# miniboard-schem.net
KiCad netlist of a schematic drawn in EAGLE
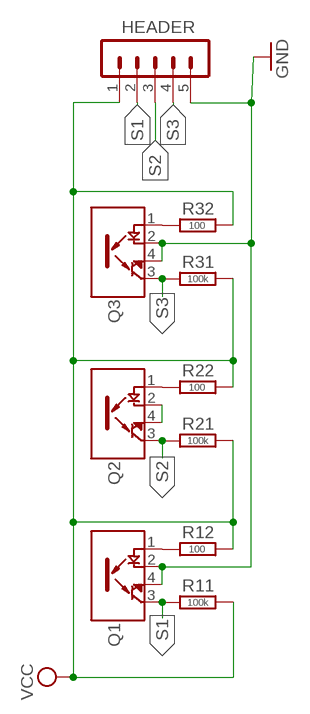
[diagram p0: schematic, sheet 1]

(export (version "E")
  (design (tool "Eeschema 10.0.6"))
  (components
    (comp (ref "HEADER")
      (value "0")
      (footprint "eagle-import:MA05-1")
      (libsource (lib "eagle-import") (part "MA05-1"))
    )
    (comp (ref "Q1")
      (value "QRE1113")
      (footprint "eagle-import:DIP400W50P180L360H200Q4")
      (fields (field (name "MANUFACTURER") "On Semiconductor"))
      (libsource (lib "eagle-import") (part "QRE1113"))
    )
    (comp (ref "Q2")
      (value "QRE1113")
      (footprint "eagle-import:DIP400W50P180L360H200Q4")
      (fields (field (name "MANUFACTURER") "On Semiconductor"))
      (libsource (lib "eagle-import") (part "QRE1113"))
    )
    (comp (ref "Q3")
      (value "QRE1113")
      (footprint "eagle-import:DIP400W50P180L360H200Q4")
      (fields (field (name "MANUFACTURER") "On Semiconductor"))
      (libsource (lib "eagle-import") (part "QRE1113"))
    )
    (comp (ref "R11")
      (value "100k")
      (footprint "eagle-import:0207_10")
      (libsource (lib "eagle-import") (part "R-EU_0207/10"))
    )
    (comp (ref "R12")
      (value "100")
      (footprint "eagle-import:0207_10")
      (libsource (lib "eagle-import") (part "R-EU_0207/10"))
    )
    (comp (ref "R21")
      (value "100k")
      (footprint "eagle-import:0207_10")
      (libsource (lib "eagle-import") (part "R-EU_0207/10"))
    )
    (comp (ref "R22")
      (value "100")
      (footprint "eagle-import:0207_10")
      (libsource (lib "eagle-import") (part "R-EU_0207/10"))
    )
    (comp (ref "R31")
      (value "100k")
      (footprint "eagle-import:0207_10")
      (libsource (lib "eagle-import") (part "R-EU_0207/10"))
    )
    (comp (ref "R32")
      (value "100")
      (footprint "eagle-import:0207_10")
      (libsource (lib "eagle-import") (part "R-EU_0207/10"))
    )
  )
  (nets
    (net (code "1") (name "GND") (class "Default")
      (node (ref "HEADER") (pin "5") (pinfunction "5_5") (pintype "passive"))
      (node (ref "Q1") (pin "2") (pinfunction "C_2") (pintype "passive"))
      (node (ref "Q1") (pin "4") (pinfunction "ET_4") (pintype "passive"))
      (node (ref "Q3") (pin "2") (pinfunction "C_2") (pintype "passive"))
      (node (ref "Q3") (pin "4") (pinfunction "ET_4") (pintype "passive"))
    )
    (net (code "2") (name "Net-(Q1-A)") (class "Default")
      (node (ref "Q1") (pin "1") (pinfunction "A_1") (pintype "passive"))
      (node (ref "R12") (pin "2") (pinfunction "2_2") (pintype "passive"))
    )
    (net (code "3") (name "Net-(Q2-A)") (class "Default")
      (node (ref "Q2") (pin "1") (pinfunction "A_1") (pintype "passive"))
      (node (ref "R22") (pin "2") (pinfunction "2_2") (pintype "passive"))
    )
    (net (code "4") (name "Net-(Q2-C)") (class "Default")
      (node (ref "Q2") (pin "2") (pinfunction "C_2") (pintype "passive"))
      (node (ref "Q2") (pin "4") (pinfunction "ET_4") (pintype "passive"))
    )
    (net (code "5") (name "Net-(Q3-A)") (class "Default")
      (node (ref "Q3") (pin "1") (pinfunction "A_1") (pintype "passive"))
      (node (ref "R32") (pin "2") (pinfunction "2_2") (pintype "passive"))
    )
    (net (code "6") (name "S1") (class "Default")
      (node (ref "HEADER") (pin "2") (pinfunction "2_2") (pintype "passive"))
      (node (ref "Q1") (pin "3") (pinfunction "CT_3") (pintype "passive"))
      (node (ref "R11") (pin "2") (pinfunction "2_2") (pintype "passive"))
    )
    (net (code "7") (name "S2") (class "Default")
      (node (ref "HEADER") (pin "3") (pinfunction "3_3") (pintype "passive"))
      (node (ref "Q2") (pin "3") (pinfunction "CT_3") (pintype "passive"))
      (node (ref "R21") (pin "2") (pinfunction "2_2") (pintype "passive"))
    )
    (net (code "8") (name "S3") (class "Default")
      (node (ref "HEADER") (pin "4") (pinfunction "4_4") (pintype "passive"))
      (node (ref "Q3") (pin "3") (pinfunction "CT_3") (pintype "passive"))
      (node (ref "R31") (pin "2") (pinfunction "2_2") (pintype "passive"))
    )
    (net (code "9") (name "VCC") (class "Default")
      (node (ref "HEADER") (pin "1") (pinfunction "1_1") (pintype "passive"))
      (node (ref "R11") (pin "1") (pinfunction "1_1") (pintype "passive"))
      (node (ref "R12") (pin "1") (pinfunction "1_1") (pintype "passive"))
      (node (ref "R21") (pin "1") (pinfunction "1_1") (pintype "passive"))
      (node (ref "R22") (pin "1") (pinfunction "1_1") (pintype "passive"))
      (node (ref "R31") (pin "1") (pinfunction "1_1") (pintype "passive"))
      (node (ref "R32") (pin "1") (pinfunction "1_1") (pintype "passive"))
    )
  )
)
